# schematic-version5_-_Jingbin.net
KiCad netlist of a schematic drawn in EAGLE
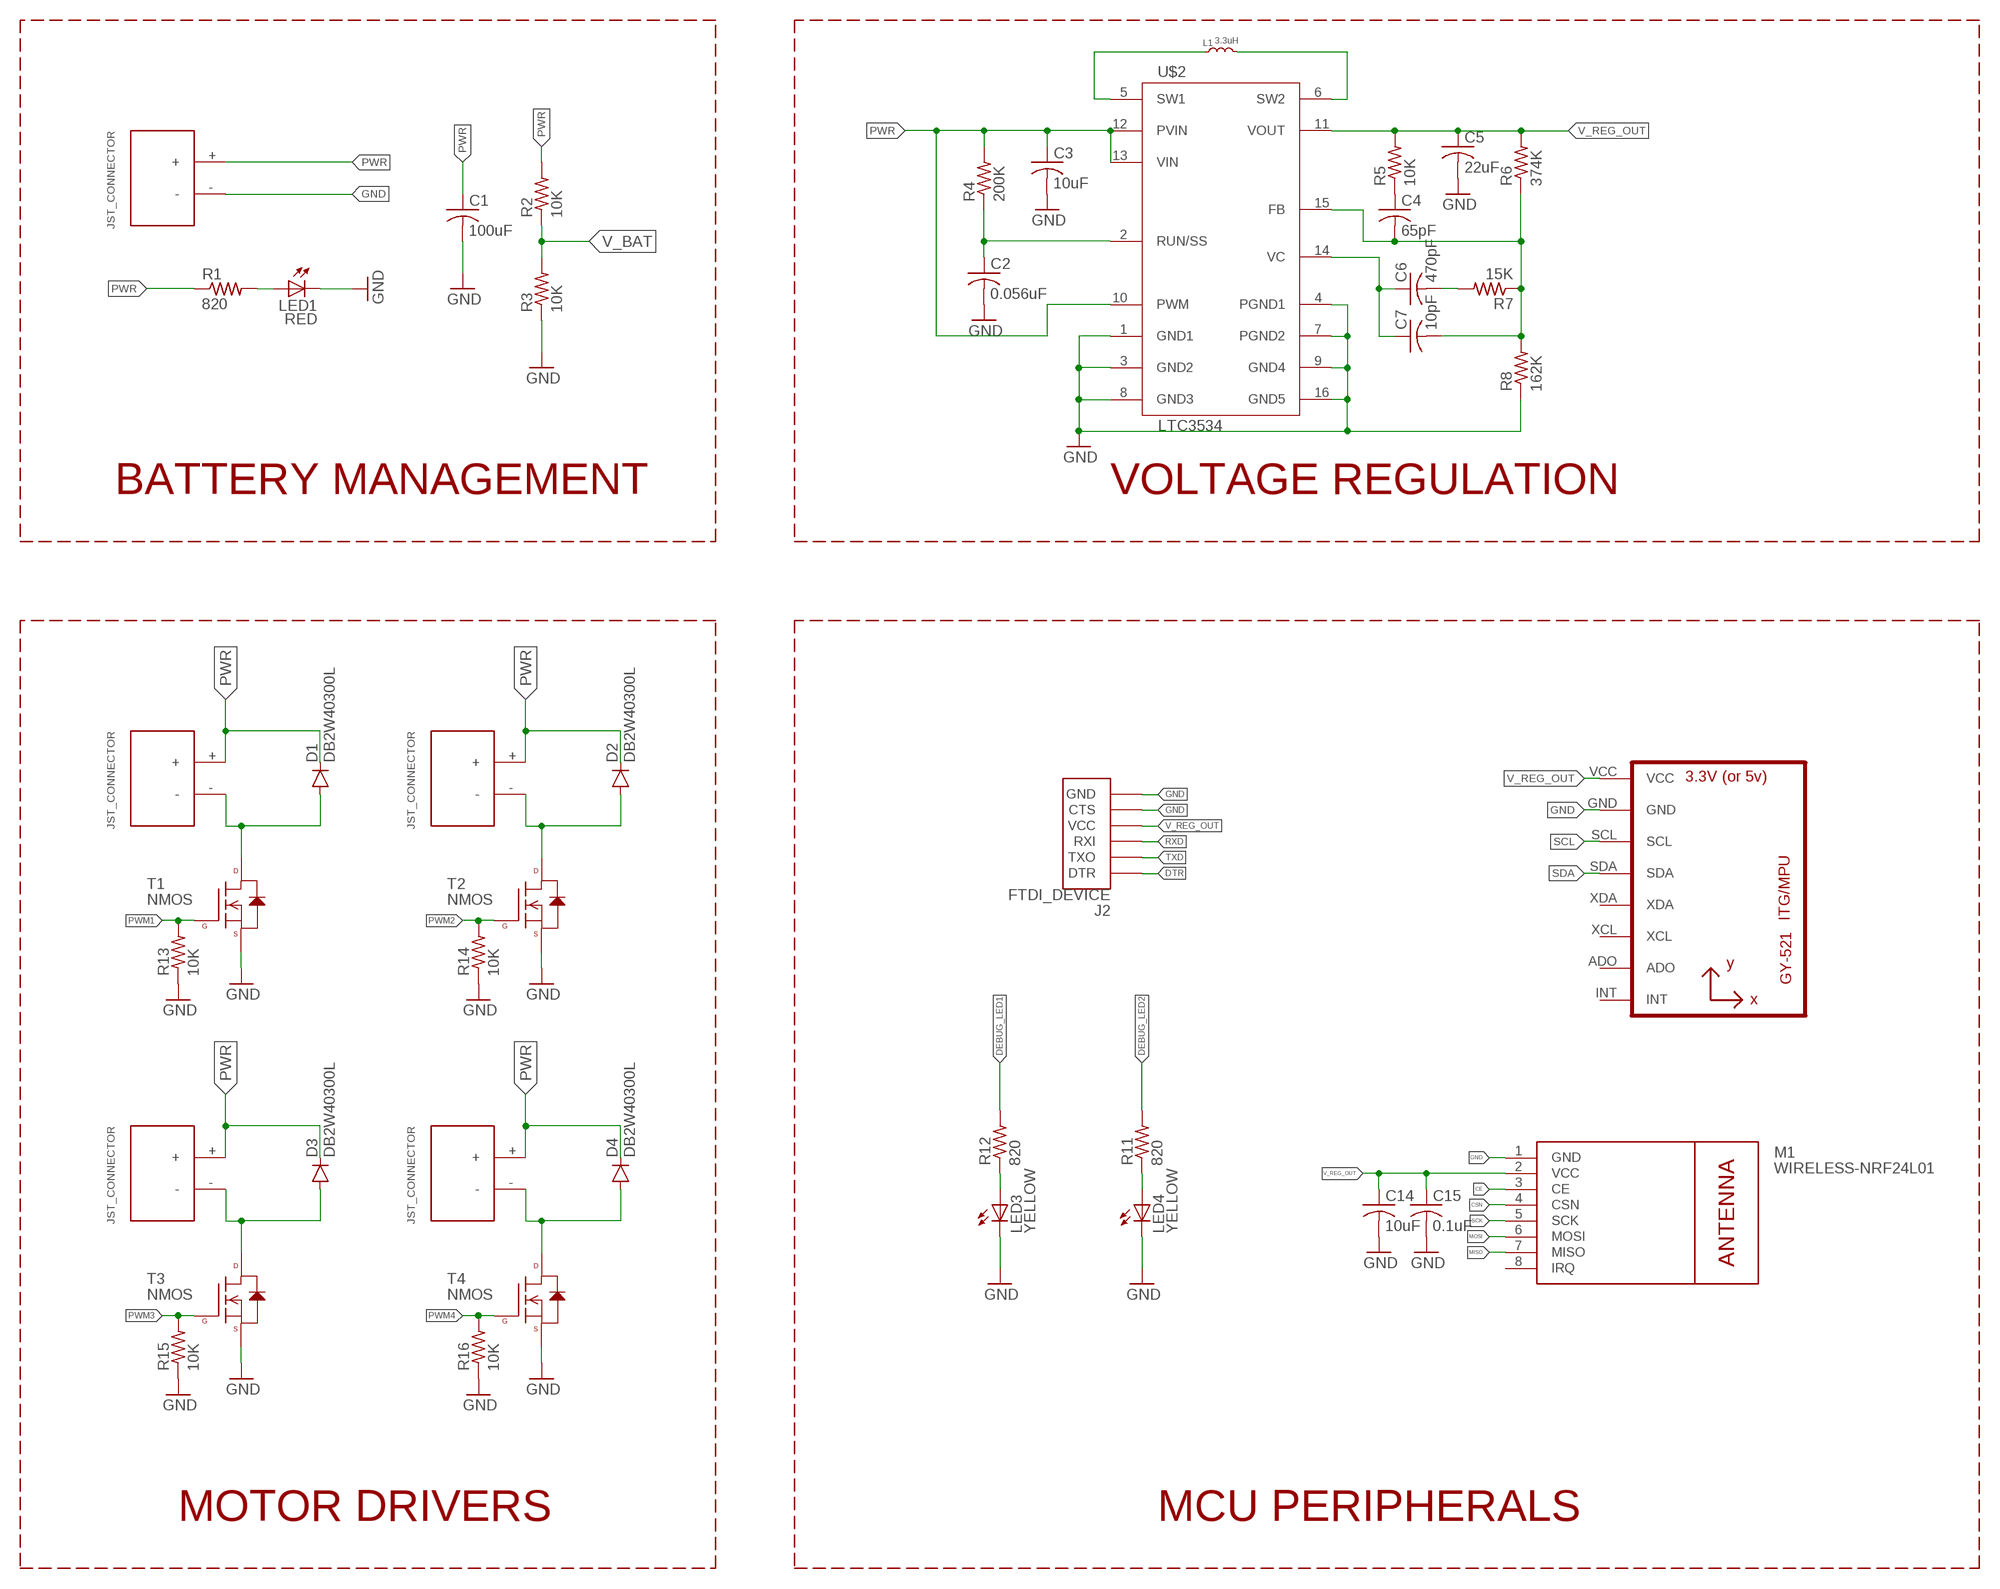
[diagram p0: schematic, sheet 1, part 1 of 2]
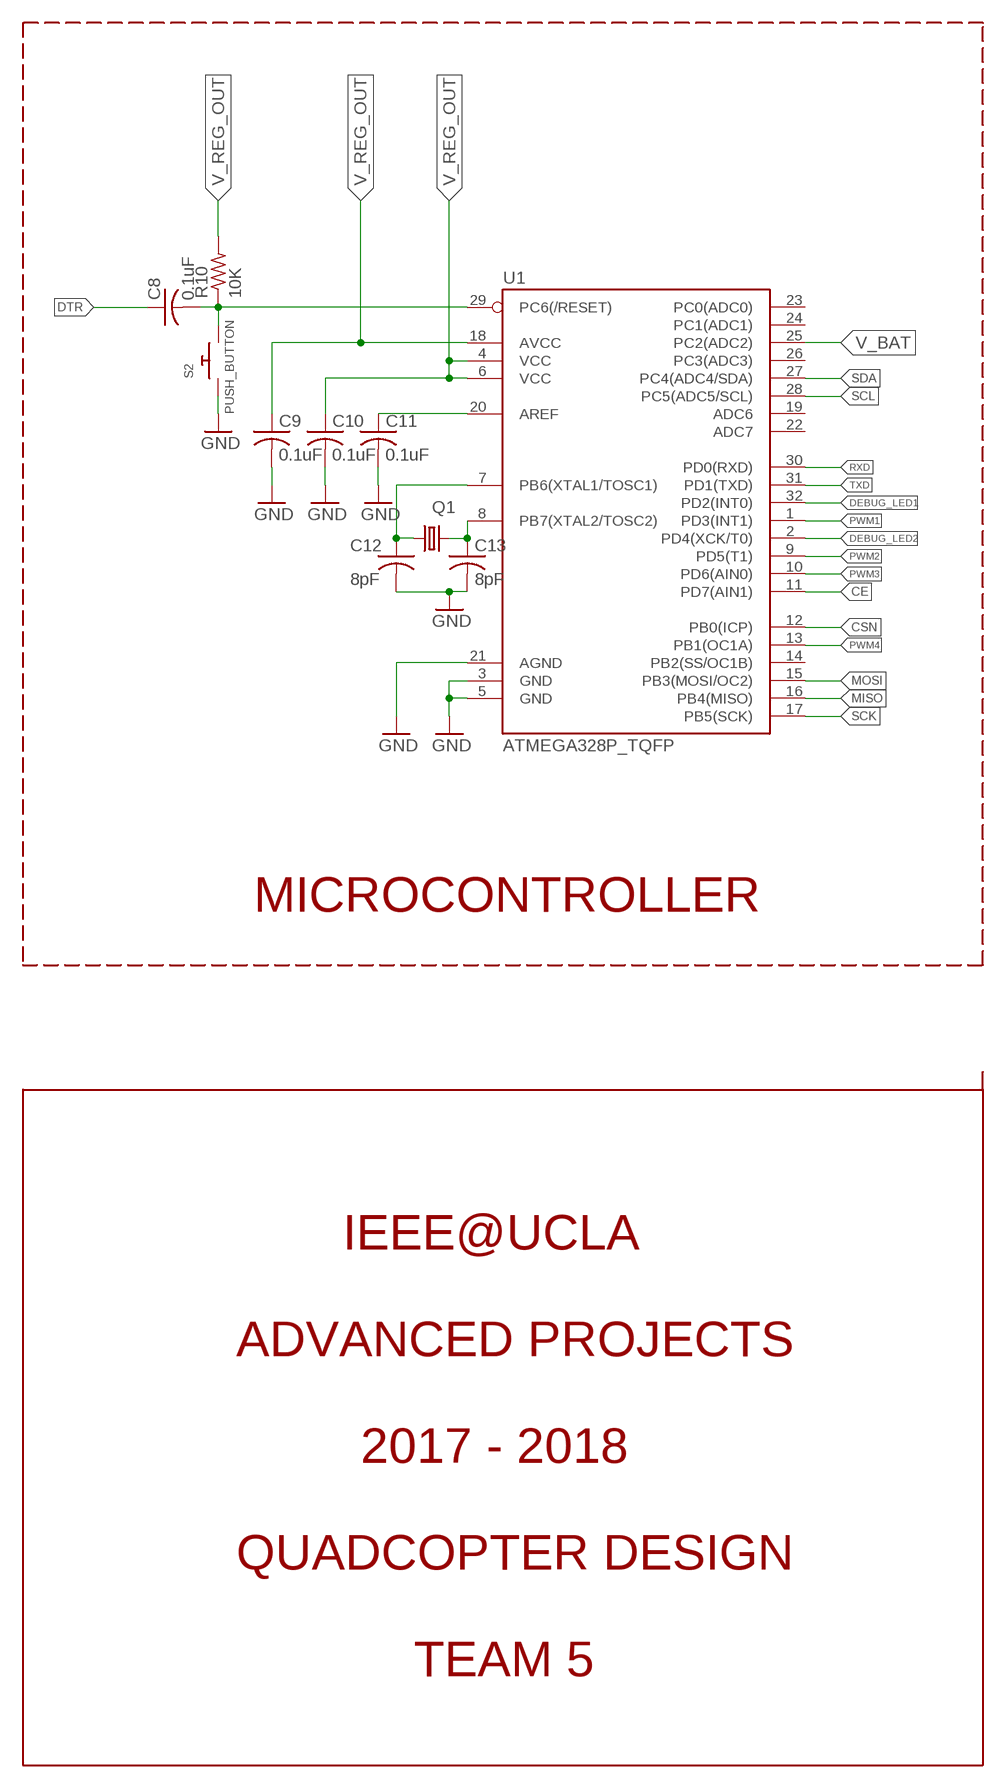
[diagram p1: schematic, sheet 1, part 2 of 2]

(export (version "E")
  (design (tool "Eeschema 10.0.6"))
  (components
    (comp (ref "C1")
      (value "100uF")
      (footprint "eagle-import:C1210")
      (libsource (lib "eagle-import") (part "C-USC1210"))
    )
    (comp (ref "C2")
      (value "0.056uF")
      (footprint "eagle-import:C0603")
      (libsource (lib "eagle-import") (part "resistor_348_C-USC0603"))
    )
    (comp (ref "C3")
      (value "10uF")
      (footprint "eagle-import:C0603")
      (libsource (lib "eagle-import") (part "resistor_348_C-USC0603"))
    )
    (comp (ref "C4")
      (value "65pF")
      (footprint "eagle-import:C1206")
      (libsource (lib "eagle-import") (part "C-USC1206"))
    )
    (comp (ref "C5")
      (value "22uF")
      (footprint "eagle-import:C0603")
      (libsource (lib "eagle-import") (part "resistor_348_C-USC0603"))
    )
    (comp (ref "C6")
      (value "470pF")
      (footprint "eagle-import:C0603")
      (libsource (lib "eagle-import") (part "resistor_348_C-USC0603"))
    )
    (comp (ref "C7")
      (value "10pF")
      (footprint "eagle-import:C0603")
      (libsource (lib "eagle-import") (part "resistor_348_C-USC0603"))
    )
    (comp (ref "C8")
      (value "0.1uF")
      (footprint "eagle-import:C0603")
      (libsource (lib "eagle-import") (part "C-USC0603"))
    )
    (comp (ref "C9")
      (value "0.1uF")
      (footprint "eagle-import:C0603")
      (libsource (lib "eagle-import") (part "C-USC0603"))
    )
    (comp (ref "C10")
      (value "0.1uF")
      (footprint "eagle-import:C0603")
      (libsource (lib "eagle-import") (part "C-USC0603"))
    )
    (comp (ref "C11")
      (value "0.1uF")
      (footprint "eagle-import:C0603")
      (libsource (lib "eagle-import") (part "C-USC0603"))
    )
    (comp (ref "C12")
      (value "8pF")
      (footprint "eagle-import:C0603")
      (libsource (lib "eagle-import") (part "resistor_348_C-USC0603"))
    )
    (comp (ref "C13")
      (value "8pF")
      (footprint "eagle-import:C0603")
      (libsource (lib "eagle-import") (part "resistor_348_C-USC0603"))
    )
    (comp (ref "C14")
      (value "10uF")
      (footprint "eagle-import:C0603")
      (libsource (lib "eagle-import") (part "resistor_348_C-USC0603"))
    )
    (comp (ref "C15")
      (value "0.1uF")
      (footprint "eagle-import:C0603")
      (libsource (lib "eagle-import") (part "resistor_348_C-USC0603"))
    )
    (comp (ref "D1")
      (value "DB2W40300L")
      (footprint "eagle-import:MINI2-F3-B")
      (libsource (lib "eagle-import") (part "DB2W40300L"))
    )
    (comp (ref "D2")
      (value "DB2W40300L")
      (footprint "eagle-import:MINI2-F3-B")
      (libsource (lib "eagle-import") (part "DB2W40300L"))
    )
    (comp (ref "D3")
      (value "DB2W40300L")
      (footprint "eagle-import:MINI2-F3-B")
      (libsource (lib "eagle-import") (part "DB2W40300L"))
    )
    (comp (ref "D4")
      (value "DB2W40300L")
      (footprint "eagle-import:MINI2-F3-B")
      (libsource (lib "eagle-import") (part "DB2W40300L"))
    )
    (comp (ref "J2")
      (value "FTDI_DEVICE")
      (footprint "eagle-import:FTDI_DEVICE_SIDE")
      (libsource (lib "eagle-import") (part "FTDI_DEVICE"))
    )
    (comp (ref "L1")
      (value "3.3uH")
      (footprint "eagle-import:XAL4020")
      (libsource (lib "eagle-import") (part "INDUCTOR.XAL4020"))
    )
    (comp (ref "LED1")
      (value "RED")
      (footprint "eagle-import:SML0603")
      (libsource (lib "eagle-import") (part "LEDSML0603"))
    )
    (comp (ref "LED3")
      (value "YELLOW")
      (footprint "eagle-import:SML0603")
      (libsource (lib "eagle-import") (part "LEDSML0603"))
    )
    (comp (ref "LED4")
      (value "YELLOW")
      (footprint "eagle-import:SML0603")
      (libsource (lib "eagle-import") (part "LEDSML0603"))
    )
    (comp (ref "M1")
      (value "WIRELESS-NRF24L01")
      (footprint "eagle-import:WIRELESS-NRF24L01")
      (libsource (lib "eagle-import") (part "WIRELESS-NRF24L01"))
    )
    (comp (ref "Q1")
      (value "NX3225GD")
      (footprint "eagle-import:NX3225GD-CRA-3")
      (libsource (lib "eagle-import") (part "NX3225GD"))
    )
    (comp (ref "R1")
      (value "820")
      (footprint "eagle-import:R0603")
      (libsource (lib "eagle-import") (part "R-US_R0603"))
    )
    (comp (ref "R2")
      (value "10K")
      (footprint "eagle-import:R0603")
      (libsource (lib "eagle-import") (part "resistor_348_R-US_R0603"))
    )
    (comp (ref "R3")
      (value "10K")
      (footprint "eagle-import:R0603")
      (libsource (lib "eagle-import") (part "resistor_348_R-US_R0603"))
    )
    (comp (ref "R4")
      (value "200K")
      (footprint "eagle-import:R0603")
      (libsource (lib "eagle-import") (part "resistor_348_R-US_R0603"))
    )
    (comp (ref "R5")
      (value "10K")
      (footprint "eagle-import:R0603")
      (libsource (lib "eagle-import") (part "resistor_348_R-US_R0603"))
    )
    (comp (ref "R6")
      (value "374K")
      (footprint "eagle-import:R0603")
      (libsource (lib "eagle-import") (part "resistor_348_R-US_R0603"))
    )
    (comp (ref "R7")
      (value "15K")
      (footprint "eagle-import:R0603")
      (libsource (lib "eagle-import") (part "resistor_348_R-US_R0603"))
    )
    (comp (ref "R8")
      (value "162K")
      (footprint "eagle-import:R0603")
      (libsource (lib "eagle-import") (part "resistor_348_R-US_R0603"))
    )
    (comp (ref "R10")
      (value "10K")
      (footprint "eagle-import:R0603")
      (libsource (lib "eagle-import") (part "resistor_348_R-US_R0603"))
    )
    (comp (ref "R11")
      (value "820")
      (footprint "eagle-import:R0603")
      (libsource (lib "eagle-import") (part "R-US_R0603"))
    )
    (comp (ref "R12")
      (value "820")
      (footprint "eagle-import:R0603")
      (libsource (lib "eagle-import") (part "R-US_R0603"))
    )
    (comp (ref "R13")
      (value "10K")
      (footprint "eagle-import:R0603")
      (libsource (lib "eagle-import") (part "resistor_348_R-US_R0603"))
    )
    (comp (ref "R14")
      (value "10K")
      (footprint "eagle-import:R0603")
      (libsource (lib "eagle-import") (part "resistor_348_R-US_R0603"))
    )
    (comp (ref "R15")
      (value "10K")
      (footprint "eagle-import:R0603")
      (libsource (lib "eagle-import") (part "resistor_348_R-US_R0603"))
    )
    (comp (ref "R16")
      (value "10K")
      (footprint "eagle-import:R0603")
      (libsource (lib "eagle-import") (part "resistor_348_R-US_R0603"))
    )
    (comp (ref "S2")
      (value "PUSH_BUTTON")
      (footprint "eagle-import:PUSHBUTTON_SMD_SJ")
      (libsource (lib "eagle-import") (part "SWITCH_PUSHBUTTONSOFTTOUCHSMD_SJ"))
    )
    (comp (ref "T1")
      (value "NMOS")
      (footprint "eagle-import:SOT23-3")
      (libsource (lib "eagle-import") (part "N-CHANNEL-MOSFET-IRLML6244TRPBF"))
    )
    (comp (ref "T2")
      (value "NMOS")
      (footprint "eagle-import:SOT23-3")
      (libsource (lib "eagle-import") (part "N-CHANNEL-MOSFET-IRLML6244TRPBF"))
    )
    (comp (ref "T3")
      (value "NMOS")
      (footprint "eagle-import:SOT23-3")
      (libsource (lib "eagle-import") (part "N-CHANNEL-MOSFET-IRLML6244TRPBF"))
    )
    (comp (ref "T4")
      (value "NMOS")
      (footprint "eagle-import:SOT23-3")
      (libsource (lib "eagle-import") (part "N-CHANNEL-MOSFET-IRLML6244TRPBF"))
    )
    (comp (ref "U$1")
      (value "JST_CONNECTOR_FEMALE")
      (footprint "eagle-import:JST_CONNECTOR_FEMALE")
      (libsource (lib "eagle-import") (part "JST_CONNECTOR_FEMALE"))
    )
    (comp (ref "U$2")
      (value "LTC3534")
      (footprint "eagle-import:SSOP-16GN")
      (libsource (lib "eagle-import") (part "LTC3534"))
    )
    (comp (ref "U$4")
      (value "JST_CONNECTOR_FEMALE")
      (footprint "eagle-import:JST_CONNECTOR_FEMALE")
      (libsource (lib "eagle-import") (part "JST_CONNECTOR_FEMALE"))
    )
    (comp (ref "U$7")
      (value "JST_CONNECTOR_FEMALE")
      (footprint "eagle-import:JST_CONNECTOR_FEMALE")
      (libsource (lib "eagle-import") (part "JST_CONNECTOR_FEMALE"))
    )
    (comp (ref "U$10")
      (value "JST_CONNECTOR_FEMALE")
      (footprint "eagle-import:JST_CONNECTOR_FEMALE")
      (libsource (lib "eagle-import") (part "JST_CONNECTOR_FEMALE"))
    )
    (comp (ref "U$13")
      (value "JST_CONNECTOR_FEMALE")
      (footprint "eagle-import:JST_CONNECTOR_FEMALE")
      (libsource (lib "eagle-import") (part "JST_CONNECTOR_FEMALE"))
    )
    (comp (ref "U1")
      (value "ATMEGA328P_TQFP")
      (footprint "eagle-import:TQFP32-08")
      (libsource (lib "eagle-import") (part "ATMEGA328P_TQFP"))
    )
    (comp (ref "U2")
      (value "GY-521MPU6050")
      (footprint "eagle-import:GY-521")
      (libsource (lib "eagle-import") (part "GY-521MPU6050"))
    )
  )
  (nets
    (net (code "1") (name "CE") (class "Default")
      (node (ref "M1") (pin "3") (pinfunction "CE_3") (pintype "bidirectional"))
      (node (ref "U1") (pin "11") (pinfunction "PD7(AIN1)_11") (pintype "bidirectional"))
    )
    (net (code "2") (name "CSN") (class "Default")
      (node (ref "M1") (pin "4") (pinfunction "CSN_4") (pintype "bidirectional"))
      (node (ref "U1") (pin "12") (pinfunction "PB0(ICP)_12") (pintype "bidirectional"))
    )
    (net (code "3") (name "DEBUG_LED1") (class "Default")
      (node (ref "R12") (pin "2") (pinfunction "2_2") (pintype "passive"))
      (node (ref "U1") (pin "32") (pinfunction "PD2(INT0)_32") (pintype "bidirectional"))
    )
    (net (code "4") (name "DEBUG_LED2") (class "Default")
      (node (ref "R11") (pin "2") (pinfunction "2_2") (pintype "passive"))
      (node (ref "U1") (pin "2") (pinfunction "PD4(XCK/T0)_2") (pintype "bidirectional"))
    )
    (net (code "5") (name "DTR") (class "Default")
      (node (ref "C8") (pin "1") (pinfunction "1_1") (pintype "passive"))
      (node (ref "J2") (pin "P$1") (pinfunction "DTR_P$1") (pintype "bidirectional"))
    )
    (net (code "6") (name "GND") (class "Default")
      (node (ref "C1") (pin "2") (pinfunction "2_2") (pintype "passive"))
      (node (ref "C10") (pin "2") (pinfunction "2_2") (pintype "passive"))
      (node (ref "C11") (pin "2") (pinfunction "2_2") (pintype "passive"))
      (node (ref "C12") (pin "2") (pinfunction "2_2") (pintype "passive"))
      (node (ref "C13") (pin "2") (pinfunction "2_2") (pintype "passive"))
      (node (ref "C14") (pin "2") (pinfunction "2_2") (pintype "passive"))
      (node (ref "C15") (pin "2") (pinfunction "2_2") (pintype "passive"))
      (node (ref "C2") (pin "2") (pinfunction "2_2") (pintype "passive"))
      (node (ref "C3") (pin "2") (pinfunction "2_2") (pintype "passive"))
      (node (ref "C5") (pin "2") (pinfunction "2_2") (pintype "passive"))
      (node (ref "C9") (pin "2") (pinfunction "2_2") (pintype "passive"))
      (node (ref "J2") (pin "P$5") (pinfunction "CTS_P$5") (pintype "bidirectional"))
      (node (ref "J2") (pin "P$6") (pinfunction "GND_P$6") (pintype "bidirectional"))
      (node (ref "LED1") (pin "C") (pinfunction "C_C") (pintype "passive"))
      (node (ref "LED3") (pin "C") (pinfunction "C_C") (pintype "passive"))
      (node (ref "LED4") (pin "C") (pinfunction "C_C") (pintype "passive"))
      (node (ref "M1") (pin "1") (pinfunction "GND_1") (pintype "power_in"))
      (node (ref "R13") (pin "1") (pinfunction "1_1") (pintype "passive"))
      (node (ref "R14") (pin "1") (pinfunction "1_1") (pintype "passive"))
      (node (ref "R15") (pin "1") (pinfunction "1_1") (pintype "passive"))
      (node (ref "R16") (pin "1") (pinfunction "1_1") (pintype "passive"))
      (node (ref "R3") (pin "1") (pinfunction "1_1") (pintype "passive"))
      (node (ref "R8") (pin "1") (pinfunction "1_1") (pintype "passive"))
      (node (ref "S2") (pin "P$1") (pinfunction "P$1_P$1") (pintype "passive"))
      (node (ref "T1") (pin "2") (pinfunction "S_2") (pintype "passive"))
      (node (ref "T2") (pin "2") (pinfunction "S_2") (pintype "passive"))
      (node (ref "T3") (pin "2") (pinfunction "S_2") (pintype "passive"))
      (node (ref "T4") (pin "2") (pinfunction "S_2") (pintype "passive"))
      (node (ref "U$1") (pin "-") (pinfunction "-_-") (pintype "bidirectional"))
      (node (ref "U$2") (pin "1") (pinfunction "GND1_1") (pintype "bidirectional"))
      (node (ref "U$2") (pin "16") (pinfunction "GND5_16") (pintype "bidirectional"))
      (node (ref "U$2") (pin "3") (pinfunction "GND2_3") (pintype "bidirectional"))
      (node (ref "U$2") (pin "4") (pinfunction "PGND1_4") (pintype "bidirectional"))
      (node (ref "U$2") (pin "7") (pinfunction "PGND2_7") (pintype "bidirectional"))
      (node (ref "U$2") (pin "8") (pinfunction "GND3_8") (pintype "bidirectional"))
      (node (ref "U$2") (pin "9") (pinfunction "GND4_9") (pintype "bidirectional"))
      (node (ref "U1") (pin "21") (pinfunction "AGND_21") (pintype "bidirectional"))
      (node (ref "U1") (pin "3") (pinfunction "GND_3") (pintype "bidirectional"))
      (node (ref "U1") (pin "5") (pinfunction "GND_5") (pintype "bidirectional"))
      (node (ref "U2") (pin "GND") (pinfunction "GND_GND") (pintype "bidirectional"))
    )
    (net (code "7") (name "MISO") (class "Default")
      (node (ref "M1") (pin "7") (pinfunction "MISO_7") (pintype "bidirectional"))
      (node (ref "U1") (pin "16") (pinfunction "PB4(MISO)_16") (pintype "bidirectional"))
    )
    (net (code "8") (name "MOSI") (class "Default")
      (node (ref "M1") (pin "6") (pinfunction "MOSI_6") (pintype "bidirectional"))
      (node (ref "U1") (pin "15") (pinfunction "PB3(MOSI/OC2)_15") (pintype "bidirectional"))
    )
    (net (code "9") (name "Net-(C4-Pad1)") (class "Default")
      (node (ref "C4") (pin "1") (pinfunction "1_1") (pintype "passive"))
      (node (ref "R5") (pin "1") (pinfunction "1_1") (pintype "passive"))
    )
    (net (code "10") (name "Net-(C6-Pad2)") (class "Default")
      (node (ref "C6") (pin "2") (pinfunction "2_2") (pintype "passive"))
      (node (ref "R7") (pin "2") (pinfunction "2_2") (pintype "passive"))
    )
    (net (code "11") (name "Net-(D1-PPIN)") (class "Default")
      (node (ref "D1") (pin "POS") (pinfunction "PPIN_POS") (pintype "passive"))
      (node (ref "T1") (pin "3") (pinfunction "D_3") (pintype "passive"))
      (node (ref "U$4") (pin "-") (pinfunction "-_-") (pintype "bidirectional"))
    )
    (net (code "12") (name "Net-(D2-PPIN)") (class "Default")
      (node (ref "D2") (pin "POS") (pinfunction "PPIN_POS") (pintype "passive"))
      (node (ref "T2") (pin "3") (pinfunction "D_3") (pintype "passive"))
      (node (ref "U$7") (pin "-") (pinfunction "-_-") (pintype "bidirectional"))
    )
    (net (code "13") (name "Net-(D3-PPIN)") (class "Default")
      (node (ref "D3") (pin "POS") (pinfunction "PPIN_POS") (pintype "passive"))
      (node (ref "T3") (pin "3") (pinfunction "D_3") (pintype "passive"))
      (node (ref "U$10") (pin "-") (pinfunction "-_-") (pintype "bidirectional"))
    )
    (net (code "14") (name "Net-(D4-PPIN)") (class "Default")
      (node (ref "D4") (pin "POS") (pinfunction "PPIN_POS") (pintype "passive"))
      (node (ref "T4") (pin "3") (pinfunction "D_3") (pintype "passive"))
      (node (ref "U$13") (pin "-") (pinfunction "-_-") (pintype "bidirectional"))
    )
    (net (code "15") (name "Net-(LED1-PadA)") (class "Default")
      (node (ref "LED1") (pin "A") (pinfunction "A_A") (pintype "passive"))
      (node (ref "R1") (pin "2") (pinfunction "2_2") (pintype "passive"))
    )
    (net (code "16") (name "Net-(LED3-PadA)") (class "Default")
      (node (ref "LED3") (pin "A") (pinfunction "A_A") (pintype "passive"))
      (node (ref "R12") (pin "1") (pinfunction "1_1") (pintype "passive"))
    )
    (net (code "17") (name "Net-(LED4-PadA)") (class "Default")
      (node (ref "LED4") (pin "A") (pinfunction "A_A") (pintype "passive"))
      (node (ref "R11") (pin "1") (pinfunction "1_1") (pintype "passive"))
    )
    (net (code "18") (name "Net-(Q1-1)") (class "Default")
      (node (ref "C12") (pin "1") (pinfunction "1_1") (pintype "passive"))
      (node (ref "Q1") (pin "P$1") (pinfunction "1_P$1") (pintype "passive"))
      (node (ref "U1") (pin "7") (pinfunction "PB6(XTAL1/TOSC1)_7") (pintype "bidirectional"))
    )
    (net (code "19") (name "Net-(Q1-2)") (class "Default")
      (node (ref "C13") (pin "1") (pinfunction "1_1") (pintype "passive"))
      (node (ref "Q1") (pin "P$2") (pinfunction "2_P$2") (pintype "passive"))
      (node (ref "U1") (pin "8") (pinfunction "PB7(XTAL2/TOSC2)_8") (pintype "bidirectional"))
    )
    (net (code "20") (name "Net-(U$2-FB)") (class "Default")
      (node (ref "C4") (pin "2") (pinfunction "2_2") (pintype "passive"))
      (node (ref "C7") (pin "2") (pinfunction "2_2") (pintype "passive"))
      (node (ref "R6") (pin "1") (pinfunction "1_1") (pintype "passive"))
      (node (ref "R7") (pin "1") (pinfunction "1_1") (pintype "passive"))
      (node (ref "R8") (pin "2") (pinfunction "2_2") (pintype "passive"))
      (node (ref "U$2") (pin "15") (pinfunction "FB_15") (pintype "bidirectional"))
    )
    (net (code "21") (name "Net-(U$2-RUN{slash}SS)") (class "Default")
      (node (ref "C2") (pin "1") (pinfunction "1_1") (pintype "passive"))
      (node (ref "R4") (pin "1") (pinfunction "1_1") (pintype "passive"))
      (node (ref "U$2") (pin "2") (pinfunction "RUN/SS_2") (pintype "bidirectional"))
    )
    (net (code "22") (name "Net-(U$2-SW1)") (class "Default")
      (node (ref "L1") (pin "1") (pinfunction "1_1") (pintype "passive"))
      (node (ref "U$2") (pin "5") (pinfunction "SW1_5") (pintype "bidirectional"))
    )
    (net (code "23") (name "Net-(U$2-SW2)") (class "Default")
      (node (ref "L1") (pin "2") (pinfunction "2_2") (pintype "passive"))
      (node (ref "U$2") (pin "6") (pinfunction "SW2_6") (pintype "bidirectional"))
    )
    (net (code "24") (name "Net-(U$2-VC)") (class "Default")
      (node (ref "C6") (pin "1") (pinfunction "1_1") (pintype "passive"))
      (node (ref "C7") (pin "1") (pinfunction "1_1") (pintype "passive"))
      (node (ref "U$2") (pin "14") (pinfunction "VC_14") (pintype "bidirectional"))
    )
    (net (code "25") (name "Net-(U1-AREF)") (class "Default")
      (node (ref "C11") (pin "1") (pinfunction "1_1") (pintype "passive"))
      (node (ref "U1") (pin "20") (pinfunction "AREF_20") (pintype "bidirectional"))
    )
    (net (code "26") (name "Net-(U1-PC6({slash}RESET))") (class "Default")
      (node (ref "C8") (pin "2") (pinfunction "2_2") (pintype "passive"))
      (node (ref "R10") (pin "1") (pinfunction "1_1") (pintype "passive"))
      (node (ref "S2") (pin "P$2") (pinfunction "P$2_P$2") (pintype "passive"))
      (node (ref "U1") (pin "29") (pinfunction "PC6(/RESET)_29") (pintype "bidirectional"))
    )
    (net (code "27") (name "PWM1") (class "Default")
      (node (ref "R13") (pin "2") (pinfunction "2_2") (pintype "passive"))
      (node (ref "T1") (pin "1") (pinfunction "G_1") (pintype "passive"))
      (node (ref "U1") (pin "1") (pinfunction "PD3(INT1)_1") (pintype "bidirectional"))
    )
    (net (code "28") (name "PWM2") (class "Default")
      (node (ref "R14") (pin "2") (pinfunction "2_2") (pintype "passive"))
      (node (ref "T2") (pin "1") (pinfunction "G_1") (pintype "passive"))
      (node (ref "U1") (pin "9") (pinfunction "PD5(T1)_9") (pintype "bidirectional"))
    )
    (net (code "29") (name "PWM3") (class "Default")
      (node (ref "R15") (pin "2") (pinfunction "2_2") (pintype "passive"))
      (node (ref "T3") (pin "1") (pinfunction "G_1") (pintype "passive"))
      (node (ref "U1") (pin "10") (pinfunction "PD6(AIN0)_10") (pintype "bidirectional"))
    )
    (net (code "30") (name "PWM4") (class "Default")
      (node (ref "R16") (pin "2") (pinfunction "2_2") (pintype "passive"))
      (node (ref "T4") (pin "1") (pinfunction "G_1") (pintype "passive"))
      (node (ref "U1") (pin "13") (pinfunction "PB1(OC1A)_13") (pintype "bidirectional"))
    )
    (net (code "31") (name "PWR") (class "Default")
      (node (ref "C1") (pin "1") (pinfunction "1_1") (pintype "passive"))
      (node (ref "C3") (pin "1") (pinfunction "1_1") (pintype "passive"))
      (node (ref "D1") (pin "NEG") (pinfunction "GPIN_NEG") (pintype "passive"))
      (node (ref "D2") (pin "NEG") (pinfunction "GPIN_NEG") (pintype "passive"))
      (node (ref "D3") (pin "NEG") (pinfunction "GPIN_NEG") (pintype "passive"))
      (node (ref "D4") (pin "NEG") (pinfunction "GPIN_NEG") (pintype "passive"))
      (node (ref "R1") (pin "1") (pinfunction "1_1") (pintype "passive"))
      (node (ref "R2") (pin "2") (pinfunction "2_2") (pintype "passive"))
      (node (ref "R4") (pin "2") (pinfunction "2_2") (pintype "passive"))
      (node (ref "U$1") (pin "+") (pinfunction "+_+") (pintype "bidirectional"))
      (node (ref "U$10") (pin "+") (pinfunction "+_+") (pintype "bidirectional"))
      (node (ref "U$13") (pin "+") (pinfunction "+_+") (pintype "bidirectional"))
      (node (ref "U$2") (pin "10") (pinfunction "PWM_10") (pintype "bidirectional"))
      (node (ref "U$2") (pin "12") (pinfunction "PVIN_12") (pintype "bidirectional"))
      (node (ref "U$2") (pin "13") (pinfunction "VIN_13") (pintype "bidirectional"))
      (node (ref "U$4") (pin "+") (pinfunction "+_+") (pintype "bidirectional"))
      (node (ref "U$7") (pin "+") (pinfunction "+_+") (pintype "bidirectional"))
    )
    (net (code "32") (name "RXD") (class "Default")
      (node (ref "J2") (pin "P$3") (pinfunction "RXI_P$3") (pintype "bidirectional"))
      (node (ref "U1") (pin "30") (pinfunction "PD0(RXD)_30") (pintype "bidirectional"))
    )
    (net (code "33") (name "SCK") (class "Default")
      (node (ref "M1") (pin "5") (pinfunction "SCK_5") (pintype "bidirectional"))
      (node (ref "U1") (pin "17") (pinfunction "PB5(SCK)_17") (pintype "bidirectional"))
    )
    (net (code "34") (name "SCL") (class "Default")
      (node (ref "U1") (pin "28") (pinfunction "PC5(ADC5/SCL)_28") (pintype "bidirectional"))
      (node (ref "U2") (pin "SCL") (pinfunction "SCL_SCL") (pintype "bidirectional"))
    )
    (net (code "35") (name "SDA") (class "Default")
      (node (ref "U1") (pin "27") (pinfunction "PC4(ADC4/SDA)_27") (pintype "bidirectional"))
      (node (ref "U2") (pin "SDA") (pinfunction "SDA_SDA") (pintype "bidirectional"))
    )
    (net (code "36") (name "TXD") (class "Default")
      (node (ref "J2") (pin "P$2") (pinfunction "TXO_P$2") (pintype "bidirectional"))
      (node (ref "U1") (pin "31") (pinfunction "PD1(TXD)_31") (pintype "bidirectional"))
    )
    (net (code "37") (name "V_BAT") (class "Default")
      (node (ref "R2") (pin "1") (pinfunction "1_1") (pintype "passive"))
      (node (ref "R3") (pin "2") (pinfunction "2_2") (pintype "passive"))
      (node (ref "U1") (pin "25") (pinfunction "PC2(ADC2)_25") (pintype "bidirectional"))
    )
    (net (code "38") (name "V_REG_OUT") (class "Default")
      (node (ref "C10") (pin "1") (pinfunction "1_1") (pintype "passive"))
      (node (ref "C14") (pin "1") (pinfunction "1_1") (pintype "passive"))
      (node (ref "C15") (pin "1") (pinfunction "1_1") (pintype "passive"))
      (node (ref "C5") (pin "1") (pinfunction "1_1") (pintype "passive"))
      (node (ref "C9") (pin "1") (pinfunction "1_1") (pintype "passive"))
      (node (ref "J2") (pin "P$4") (pinfunction "VCC_P$4") (pintype "bidirectional"))
      (node (ref "M1") (pin "2") (pinfunction "VCC_2") (pintype "power_in"))
      (node (ref "R10") (pin "2") (pinfunction "2_2") (pintype "passive"))
      (node (ref "R5") (pin "2") (pinfunction "2_2") (pintype "passive"))
      (node (ref "R6") (pin "2") (pinfunction "2_2") (pintype "passive"))
      (node (ref "U$2") (pin "11") (pinfunction "VOUT_11") (pintype "bidirectional"))
      (node (ref "U1") (pin "18") (pinfunction "AVCC_18") (pintype "bidirectional"))
      (node (ref "U1") (pin "4") (pinfunction "VCC_4") (pintype "bidirectional"))
      (node (ref "U1") (pin "6") (pinfunction "VCC_6") (pintype "bidirectional"))
      (node (ref "U2") (pin "VCC") (pinfunction "VCC_VCC") (pintype "bidirectional"))
    )
    (net (code "39") (name "unconnected-(M1-IRQ-Pad8)") (class "Default")
      (node (ref "M1") (pin "8") (pinfunction "IRQ_8") (pintype "bidirectional"))
    )
    (net (code "40") (name "unconnected-(U1-ADC6-Pad19)") (class "Default")
      (node (ref "U1") (pin "19") (pinfunction "ADC6_19") (pintype "bidirectional"))
    )
    (net (code "41") (name "unconnected-(U1-ADC7-Pad22)") (class "Default")
      (node (ref "U1") (pin "22") (pinfunction "ADC7_22") (pintype "bidirectional"))
    )
    (net (code "42") (name "unconnected-(U1-PB2(SS{slash}OC1B)-Pad14)") (class "Default")
      (node (ref "U1") (pin "14") (pinfunction "PB2(SS/OC1B)_14") (pintype "bidirectional"))
    )
    (net (code "43") (name "unconnected-(U1-PC0(ADC0)-Pad23)") (class "Default")
      (node (ref "U1") (pin "23") (pinfunction "PC0(ADC0)_23") (pintype "bidirectional"))
    )
    (net (code "44") (name "unconnected-(U1-PC1(ADC1)-Pad24)") (class "Default")
      (node (ref "U1") (pin "24") (pinfunction "PC1(ADC1)_24") (pintype "bidirectional"))
    )
    (net (code "45") (name "unconnected-(U1-PC3(ADC3)-Pad26)") (class "Default")
      (node (ref "U1") (pin "26") (pinfunction "PC3(ADC3)_26") (pintype "bidirectional"))
    )
    (net (code "46") (name "unconnected-(U2-PadADO)") (class "Default")
      (node (ref "U2") (pin "ADO") (pinfunction "ADO_ADO") (pintype "bidirectional"))
    )
    (net (code "47") (name "unconnected-(U2-PadINT)") (class "Default")
      (node (ref "U2") (pin "INT") (pinfunction "INT_INT") (pintype "bidirectional"))
    )
    (net (code "48") (name "unconnected-(U2-PadXCL)") (class "Default")
      (node (ref "U2") (pin "XCL") (pinfunction "XCL_XCL") (pintype "bidirectional"))
    )
    (net (code "49") (name "unconnected-(U2-PadXDA)") (class "Default")
      (node (ref "U2") (pin "XDA") (pinfunction "XDA_XDA") (pintype "bidirectional"))
    )
  )
)
